# Adafruit_Feather_M0_Adalogger.net
KiCad netlist of a schematic drawn in Altium Designer
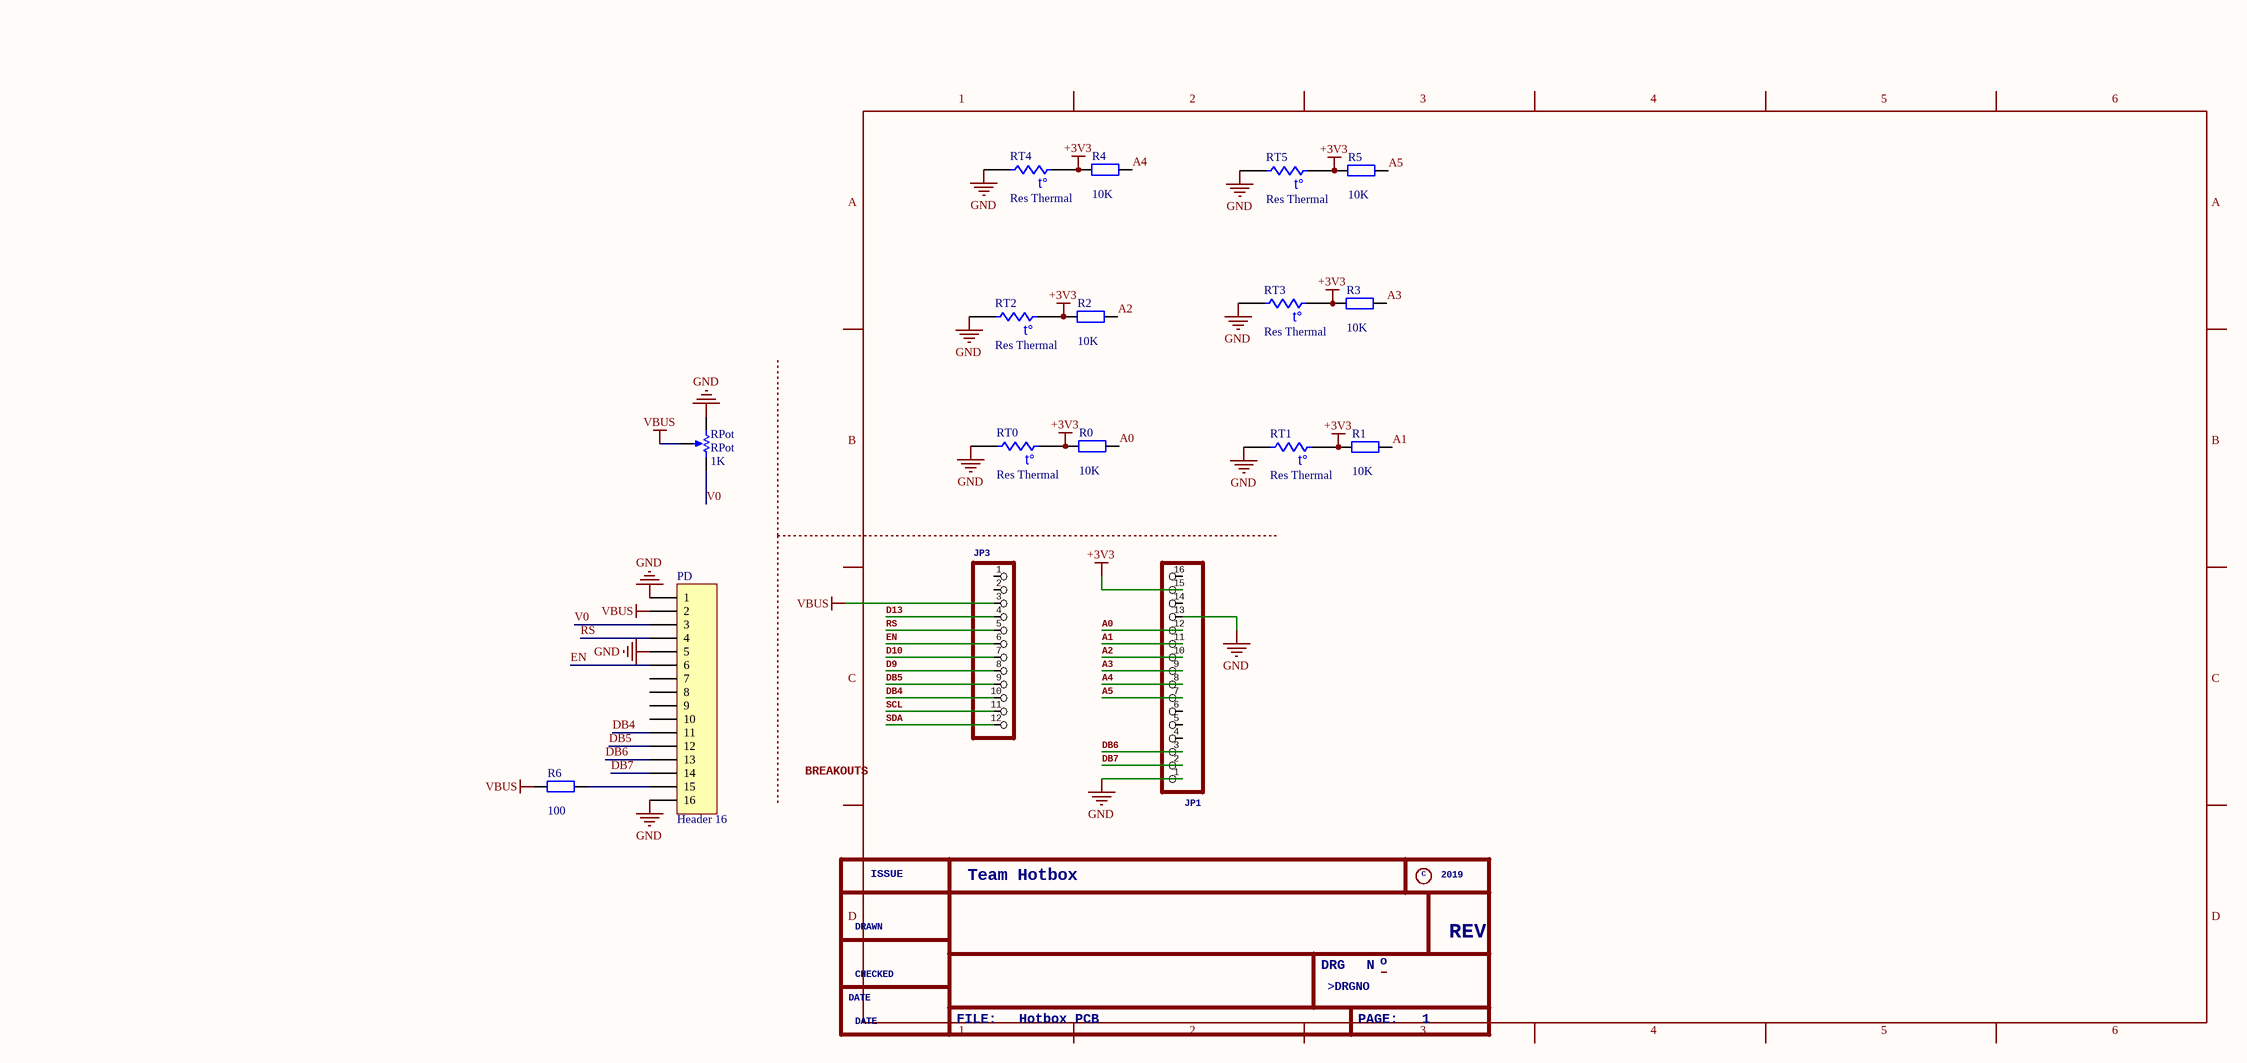
[diagram p0: Adafruit Feather M0 Adalogger.SchDoc]

(export (version "E")
  (design (tool "Eeschema 10.0.6"))
  (components
    (comp (ref "FRAME1")
      (value "FRAME_A4")
      (description "FRAME   DIN A4, landscape with location and doc. field")
      (fields
        (field (name "SHEET") "1")
        (field (name "DRG") "DRG")
        (field (name "O") "o")
        (field (name "TITLE") "Hotbox PCB")
        (field (name "N") "N")
        (field (name "2019") "2019")
        (field (name "C") "C")
        (field (name "ISSUE") "ISSUE")
        (field (name "DATE") "DATE")
        (field (name "COMPANY") "Team Hotbox")
        (field (name "FILE") "FILE:")
        (field (name "PAGE") "PAGE:")
        (field (name "DRAWN") "DRAWN")
        (field (name "CHECKED") "CHECKED")
        (field (name "DATE_1") "DATE")
        (field (name "DRGNO") ">DRGNO")
        (field (name "REV") "REV")
      )
      (libsource (lib "microbuilder") (part "FRAME_A4"))
    )
    (comp (ref "JP1")
      (value "HEADER-1X16ROUND")
      (footprint "1X16_ROUND")
      (description "PIN HEADER")
      (libsource (lib "microbuilder") (part "HEADER-1X16ROUND"))
    )
    (comp (ref "JP3")
      (value "HEADER-1X12")
      (footprint "1X12_ROUND")
      (libsource (lib "microbuilder") (part "HEADER-1X12"))
    )
    (comp (ref "PD")
      (value "Header 16")
      (footprint "HDR1X16")
      (description "Header, 16-Pin")
      (fields (field (name "PUBLISHER") "Altium Limited"))
      (libsource (lib "Miscellaneous Connectors") (part "Header 16"))
    )
    (comp (ref "R0")
      (value "10K")
      (footprint "AXIAL-0.4")
      (description "Resistor")
      (fields (field (name "PUBLISHER") "Altium Limited"))
      (libsource (lib "Miscellaneous Devices") (part "Res2"))
    )
    (comp (ref "R1")
      (value "10K")
      (footprint "AXIAL-0.4")
      (description "Resistor")
      (fields (field (name "PUBLISHER") "Altium Limited"))
      (libsource (lib "Miscellaneous Devices") (part "Res2"))
    )
    (comp (ref "R2")
      (value "10K")
      (footprint "AXIAL-0.4")
      (description "Resistor")
      (fields (field (name "PUBLISHER") "Altium Limited"))
      (libsource (lib "Miscellaneous Devices") (part "Res2"))
    )
    (comp (ref "R3")
      (value "10K")
      (footprint "AXIAL-0.4")
      (description "Resistor")
      (fields (field (name "PUBLISHER") "Altium Limited"))
      (libsource (lib "Miscellaneous Devices") (part "Res2"))
    )
    (comp (ref "R4")
      (value "10K")
      (footprint "AXIAL-0.4")
      (description "Resistor")
      (fields (field (name "PUBLISHER") "Altium Limited"))
      (libsource (lib "Miscellaneous Devices") (part "Res2"))
    )
    (comp (ref "R5")
      (value "10K")
      (footprint "AXIAL-0.4")
      (description "Resistor")
      (fields (field (name "PUBLISHER") "Altium Limited"))
      (libsource (lib "Miscellaneous Devices") (part "Res2"))
    )
    (comp (ref "R6")
      (value "100")
      (footprint "AXIAL-0.4")
      (description "Resistor")
      (fields (field (name "PUBLISHER") "Altium Limited"))
      (libsource (lib "Miscellaneous Devices") (part "Res2"))
    )
    (comp (ref "RPot")
      (value "RPot")
      (footprint "VR4")
      (description "Potentiometer")
      (fields (field (name "ALTIUM_VALUE") "1K") (field (name "PUBLISHER") "Altium Limited"))
      (libsource (lib "Miscellaneous Devices") (part "RPot"))
    )
    (comp (ref "RT0")
      (value "Res Thermal")
      (footprint "PIN-W2/E2.8")
      (description "Thermistor")
      (fields (field (name "PUBLISHER") "Altium Limited"))
      (libsource (lib "Miscellaneous Devices") (part "Res Thermal"))
    )
    (comp (ref "RT1")
      (value "Res Thermal")
      (footprint "PIN-W2/E2.8")
      (description "Thermistor")
      (fields (field (name "PUBLISHER") "Altium Limited"))
      (libsource (lib "Miscellaneous Devices") (part "Res Thermal"))
    )
    (comp (ref "RT2")
      (value "Res Thermal")
      (footprint "PIN-W2/E2.8")
      (description "Thermistor")
      (fields (field (name "PUBLISHER") "Altium Limited"))
      (libsource (lib "Miscellaneous Devices") (part "Res Thermal"))
    )
    (comp (ref "RT3")
      (value "Res Thermal")
      (footprint "PIN-W2/E2.8")
      (description "Thermistor")
      (fields (field (name "PUBLISHER") "Altium Limited"))
      (libsource (lib "Miscellaneous Devices") (part "Res Thermal"))
    )
    (comp (ref "RT4")
      (value "Res Thermal")
      (footprint "PIN-W2/E2.8")
      (description "Thermistor")
      (fields (field (name "PUBLISHER") "Altium Limited"))
      (libsource (lib "Miscellaneous Devices") (part "Res Thermal"))
    )
    (comp (ref "RT5")
      (value "Res Thermal")
      (footprint "PIN-W2/E2.8")
      (description "Thermistor")
      (fields (field (name "PUBLISHER") "Altium Limited"))
      (libsource (lib "Miscellaneous Devices") (part "Res Thermal"))
    )
  )
  (nets
    (net (code "1") (name "+3V3") (class "Default")
      (node (ref "JP1") (pin "15") (pinfunction "15_15") (pintype "passive"))
      (node (ref "R0") (pin "1") (pinfunction "1_1") (pintype "passive"))
      (node (ref "R1") (pin "1") (pinfunction "1_1") (pintype "passive"))
      (node (ref "R2") (pin "1") (pinfunction "1_1") (pintype "passive"))
      (node (ref "R3") (pin "1") (pinfunction "1_1") (pintype "passive"))
      (node (ref "R4") (pin "1") (pinfunction "1_1") (pintype "passive"))
      (node (ref "R5") (pin "1") (pinfunction "1_1") (pintype "passive"))
      (node (ref "RT0") (pin "1") (pinfunction "1_1") (pintype "passive"))
      (node (ref "RT1") (pin "1") (pinfunction "1_1") (pintype "passive"))
      (node (ref "RT2") (pin "1") (pinfunction "1_1") (pintype "passive"))
      (node (ref "RT3") (pin "1") (pinfunction "1_1") (pintype "passive"))
      (node (ref "RT4") (pin "1") (pinfunction "1_1") (pintype "passive"))
      (node (ref "RT5") (pin "1") (pinfunction "1_1") (pintype "passive"))
    )
    (net (code "3") (name "/A0") (class "Default")
      (node (ref "JP1") (pin "12") (pinfunction "12_12") (pintype "passive"))
      (node (ref "R0") (pin "2") (pinfunction "2_2") (pintype "passive"))
    )
    (net (code "4") (name "/A1") (class "Default")
      (node (ref "JP1") (pin "11") (pinfunction "11_11") (pintype "passive"))
      (node (ref "R1") (pin "2") (pinfunction "2_2") (pintype "passive"))
    )
    (net (code "5") (name "/A2") (class "Default")
      (node (ref "JP1") (pin "10") (pinfunction "10_10") (pintype "passive"))
      (node (ref "R2") (pin "2") (pinfunction "2_2") (pintype "passive"))
    )
    (net (code "6") (name "/A3") (class "Default")
      (node (ref "JP1") (pin "9") (pinfunction "9_9") (pintype "passive"))
      (node (ref "R3") (pin "2") (pinfunction "2_2") (pintype "passive"))
    )
    (net (code "7") (name "/A4") (class "Default")
      (node (ref "JP1") (pin "8") (pinfunction "8_8") (pintype "passive"))
      (node (ref "R4") (pin "2") (pinfunction "2_2") (pintype "passive"))
    )
    (net (code "8") (name "/A5") (class "Default")
      (node (ref "JP1") (pin "7") (pinfunction "7_7") (pintype "passive"))
      (node (ref "R5") (pin "2") (pinfunction "2_2") (pintype "passive"))
    )
    (net (code "9") (name "/D9") (class "Default")
      (node (ref "JP3") (pin "8") (pinfunction "8_8") (pintype "passive"))
    )
    (net (code "10") (name "/D10") (class "Default")
      (node (ref "JP3") (pin "7") (pinfunction "7_7") (pintype "passive"))
    )
    (net (code "11") (name "/D13") (class "Default")
      (node (ref "JP3") (pin "4") (pinfunction "4_4") (pintype "passive"))
    )
    (net (code "12") (name "/DB4") (class "Default")
      (node (ref "JP3") (pin "10") (pinfunction "10_10") (pintype "passive"))
      (node (ref "PD") (pin "11") (pinfunction "11_11") (pintype "passive"))
    )
    (net (code "13") (name "/DB5") (class "Default")
      (node (ref "JP3") (pin "9") (pinfunction "9_9") (pintype "passive"))
      (node (ref "PD") (pin "12") (pinfunction "12_12") (pintype "passive"))
    )
    (net (code "14") (name "/DB6") (class "Default")
      (node (ref "JP1") (pin "3") (pinfunction "3_3") (pintype "passive"))
      (node (ref "PD") (pin "13") (pinfunction "13_13") (pintype "passive"))
    )
    (net (code "15") (name "/DB7") (class "Default")
      (node (ref "JP1") (pin "2") (pinfunction "2_2") (pintype "passive"))
      (node (ref "PD") (pin "14") (pinfunction "14_14") (pintype "passive"))
    )
    (net (code "16") (name "/EN") (class "Default")
      (node (ref "JP3") (pin "6") (pinfunction "6_6") (pintype "passive"))
      (node (ref "PD") (pin "6") (pinfunction "6_6") (pintype "passive"))
    )
    (net (code "17") (name "/RS") (class "Default")
      (node (ref "JP3") (pin "5") (pinfunction "5_5") (pintype "passive"))
      (node (ref "PD") (pin "4") (pinfunction "4_4") (pintype "passive"))
    )
    (net (code "18") (name "/SCL") (class "Default")
      (node (ref "JP3") (pin "11") (pinfunction "11_11") (pintype "passive"))
    )
    (net (code "19") (name "/SDA") (class "Default")
      (node (ref "JP3") (pin "12") (pinfunction "12_12") (pintype "passive"))
    )
    (net (code "20") (name "/V0") (class "Default")
      (node (ref "PD") (pin "3") (pinfunction "3_3") (pintype "passive"))
      (node (ref "RPot") (pin "2") (pinfunction "BOT_2") (pintype "passive"))
    )
    (net (code "21") (name "GND") (class "Default")
      (node (ref "JP1") (pin "1") (pinfunction "1_1") (pintype "passive"))
      (node (ref "JP1") (pin "13") (pinfunction "13_13") (pintype "passive"))
      (node (ref "PD") (pin "1") (pinfunction "1_1") (pintype "passive"))
      (node (ref "PD") (pin "16") (pinfunction "16_16") (pintype "passive"))
      (node (ref "PD") (pin "5") (pinfunction "5_5") (pintype "passive"))
      (node (ref "RPot") (pin "1") (pinfunction "TOP_1") (pintype "passive"))
      (node (ref "RT0") (pin "2") (pinfunction "2_2") (pintype "passive"))
      (node (ref "RT1") (pin "2") (pinfunction "2_2") (pintype "passive"))
      (node (ref "RT2") (pin "2") (pinfunction "2_2") (pintype "passive"))
      (node (ref "RT3") (pin "2") (pinfunction "2_2") (pintype "passive"))
      (node (ref "RT4") (pin "2") (pinfunction "2_2") (pintype "passive"))
      (node (ref "RT5") (pin "2") (pinfunction "2_2") (pintype "passive"))
    )
    (net (code "22") (name "Net-(PD-Pad15)") (class "Default")
      (node (ref "PD") (pin "15") (pinfunction "15_15") (pintype "passive"))
      (node (ref "R6") (pin "2") (pinfunction "2_2") (pintype "passive"))
    )
    (net (code "23") (name "VBUS") (class "Default")
      (node (ref "JP3") (pin "3") (pinfunction "3_3") (pintype "passive"))
      (node (ref "PD") (pin "2") (pinfunction "2_2") (pintype "passive"))
      (node (ref "R6") (pin "1") (pinfunction "1_1") (pintype "passive"))
      (node (ref "RPot") (pin "3") (pinfunction "TAP_3") (pintype "passive"))
    )
    (net (code "24") (name "unconnected-(JP1-Pad4)") (class "Default")
      (node (ref "JP1") (pin "4") (pinfunction "4_4") (pintype "passive"))
    )
    (net (code "25") (name "unconnected-(JP1-Pad5)") (class "Default")
      (node (ref "JP1") (pin "5") (pinfunction "5_5") (pintype "passive"))
    )
    (net (code "26") (name "unconnected-(JP1-Pad6)") (class "Default")
      (node (ref "JP1") (pin "6") (pinfunction "6_6") (pintype "passive"))
    )
    (net (code "27") (name "unconnected-(JP1-Pad14)") (class "Default")
      (node (ref "JP1") (pin "14") (pinfunction "14_14") (pintype "passive"))
    )
    (net (code "28") (name "unconnected-(JP1-Pad16)") (class "Default")
      (node (ref "JP1") (pin "16") (pinfunction "16_16") (pintype "passive"))
    )
    (net (code "29") (name "unconnected-(JP3-Pad1)") (class "Default")
      (node (ref "JP3") (pin "1") (pinfunction "1_1") (pintype "passive"))
    )
    (net (code "30") (name "unconnected-(JP3-Pad2)") (class "Default")
      (node (ref "JP3") (pin "2") (pinfunction "2_2") (pintype "passive"))
    )
    (net (code "31") (name "unconnected-(PD-Pad7)") (class "Default")
      (node (ref "PD") (pin "7") (pinfunction "7_7") (pintype "passive"))
    )
    (net (code "32") (name "unconnected-(PD-Pad8)") (class "Default")
      (node (ref "PD") (pin "8") (pinfunction "8_8") (pintype "passive"))
    )
    (net (code "33") (name "unconnected-(PD-Pad9)") (class "Default")
      (node (ref "PD") (pin "9") (pinfunction "9_9") (pintype "passive"))
    )
    (net (code "34") (name "unconnected-(PD-Pad10)") (class "Default")
      (node (ref "PD") (pin "10") (pinfunction "10_10") (pintype "passive"))
    )
  )
)
